# 1_P1.net
KiCad netlist of a schematic drawn in Altium Designer
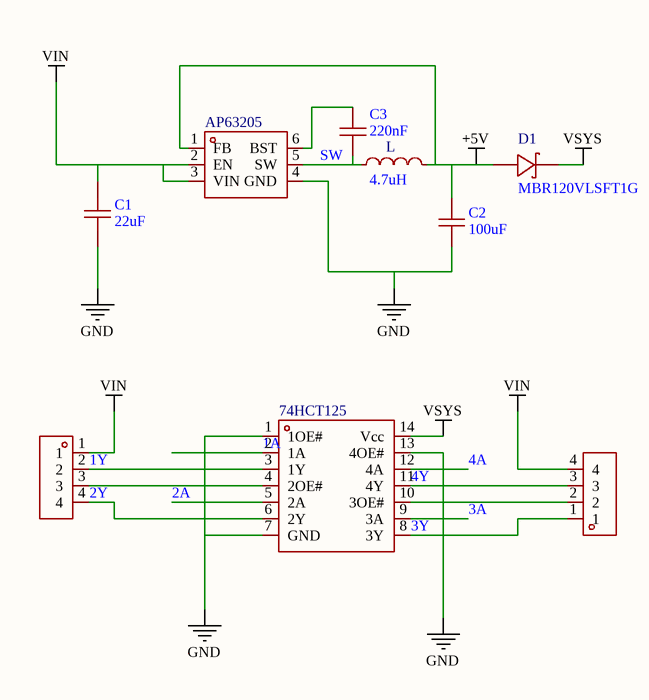
[diagram p0: 1_P1.schdoc]

(export (version "E")
  (design (tool "Eeschema 10.0.6"))
  (components
    (comp (ref "74HCT125")
      (value "74HCT125T14-13")
      (footprint "TSSOP-14_L5.0-W4.4-P0.65-LS6.4-BL")
      (fields (field (name "MANUFACTURER") "DIODES(美台)"))
      (libsource (lib "altium-import") (part "root_0_74HCT125T14-13_"))
    )
    (comp (ref "AP63205")
      (value "AP63205WU-7")
      (footprint "TSOT-23-6_L2.9-W1.6-P0.95-LS2.8-BL")
      (fields (field (name "MANUFACTURER") "DIODES(美台)"))
      (libsource (lib "altium-import") (part "root_0_AP63205WU-7_"))
    )
    (comp (ref "C1")
      (value "22uF")
      (footprint "C1210")
      (fields
        (field (name "MANUFACTURER") "TAIYO YUDEN(太诱)")
        (field (name "MANUFACTURER PART") "GMK325BJ226MM-P")
        (field (name "TOLERANCE") "±20%")
      )
      (libsource (lib "altium-import") (part "root_1_GMK325BJ226MM-P_"))
    )
    (comp (ref "C2")
      (value "100uF")
      (footprint "C1210")
      (fields
        (field (name "MANUFACTURER") "SAMSUNG(三星)")
        (field (name "MANUFACTURER PART") "CL32A107MQVNNNE")
        (field (name "TOLERANCE") "±20%")
      )
      (libsource (lib "altium-import") (part "root_1_CL32A107MQVNNNE_"))
    )
    (comp (ref "C3")
      (value "220nF")
      (footprint "C0603")
      (fields
        (field (name "MANUFACTURER") "SAMSUNG(三星)")
        (field (name "MANUFACTURER PART") "CL10B224KB8NNNC")
        (field (name "TOLERANCE") "±10%")
      )
      (libsource (lib "altium-import") (part "root_1_CL10B224KB8NNNC_"))
    )
    (comp (ref "CN1")
      (value "DB125-3.5-4P-GN-S")
      (footprint "CONN-TH_DB125-3.5-4P-GN")
      (fields (field (name "MANUFACTURER") "DORABO(地博电气)"))
      (libsource (lib "altium-import") (part "root_0_mirrored_DB125-3.5-4P-GN-S_"))
    )
    (comp (ref "CN2")
      (value "DB125-3.5-4P-GN-S")
      (footprint "CONN-TH_DB125-3.5-4P-GN")
      (fields (field (name "MANUFACTURER") "DORABO(地博电气)"))
      (libsource (lib "altium-import") (part "root_2_mirrored_DB125-3.5-4P-GN-S_"))
    )
    (comp (ref "D1")
      (value "MBR120VLSFT1G")
      (footprint "SOD-123F_L2.8-W1.8-LS3.7-RD")
      (fields (field (name "MANUFACTURER") "onsemi(安森美)"))
      (libsource (lib "altium-import") (part "root_0_mirrored_MBR120VLSFT1G_"))
    )
    (comp (ref "L")
      (value "4.7uH")
      (footprint "IND-SMD_L4.0-W4.0")
      (fields
        (field (name "MANUFACTURER") "ceaiya(柯爱亚)")
        (field (name "MANUFACTURER PART") "CR4030-4R7M")
        (field (name "TOLERANCE") "±20%")
      )
      (libsource (lib "altium-import") (part "root_0_CR4030-4R7M_"))
    )
  )
  (nets
    (net (code "1") (name "+5V") (class "Default")
      (node (ref "AP63205") (pin "1") (pinfunction "FB_1") (pintype "passive"))
      (node (ref "C2") (pin "2") (pinfunction "2_2") (pintype "passive"))
      (node (ref "D1") (pin "2") (pinfunction "A_2") (pintype "passive"))
      (node (ref "L") (pin "2") (pinfunction "2_2") (pintype "passive"))
    )
    (net (code "2") (name "/1A") (class "Default")
      (node (ref "74HCT125") (pin "2") (pinfunction "1A_2") (pintype "passive"))
    )
    (net (code "3") (name "/1Y") (class "Default")
      (node (ref "74HCT125") (pin "3") (pinfunction "1Y_3") (pintype "passive"))
      (node (ref "CN1") (pin "2") (pinfunction "2_2") (pintype "passive"))
    )
    (net (code "4") (name "/2A") (class "Default")
      (node (ref "74HCT125") (pin "5") (pinfunction "2A_5") (pintype "passive"))
    )
    (net (code "5") (name "/2Y") (class "Default")
      (node (ref "74HCT125") (pin "6") (pinfunction "2Y_6") (pintype "passive"))
      (node (ref "CN1") (pin "4") (pinfunction "4_4") (pintype "passive"))
    )
    (net (code "6") (name "/3A") (class "Default")
      (node (ref "74HCT125") (pin "9") (pinfunction "3A_9") (pintype "passive"))
    )
    (net (code "7") (name "/3Y") (class "Default")
      (node (ref "74HCT125") (pin "8") (pinfunction "3Y_8") (pintype "passive"))
      (node (ref "CN2") (pin "1") (pinfunction "1_1") (pintype "passive"))
    )
    (net (code "8") (name "/4A") (class "Default")
      (node (ref "74HCT125") (pin "12") (pinfunction "4A_12") (pintype "passive"))
    )
    (net (code "9") (name "/4Y") (class "Default")
      (node (ref "74HCT125") (pin "11") (pinfunction "4Y_11") (pintype "passive"))
      (node (ref "CN2") (pin "3") (pinfunction "3_3") (pintype "passive"))
    )
    (net (code "10") (name "/SW") (class "Default")
      (node (ref "AP63205") (pin "5") (pinfunction "SW_5") (pintype "passive"))
      (node (ref "C3") (pin "1") (pinfunction "1_1") (pintype "passive"))
      (node (ref "L") (pin "1") (pinfunction "1_1") (pintype "passive"))
    )
    (net (code "11") (name "GND") (class "Default")
      (node (ref "74HCT125") (pin "1") (pinfunction "1OE#_1") (pintype "passive"))
      (node (ref "74HCT125") (pin "10") (pinfunction "3OE#_10") (pintype "passive"))
      (node (ref "74HCT125") (pin "13") (pinfunction "4OE#_13") (pintype "passive"))
      (node (ref "74HCT125") (pin "4") (pinfunction "2OE#_4") (pintype "passive"))
      (node (ref "74HCT125") (pin "7") (pinfunction "GND_7") (pintype "passive"))
      (node (ref "AP63205") (pin "4") (pinfunction "GND_4") (pintype "passive"))
      (node (ref "C1") (pin "1") (pinfunction "1_1") (pintype "passive"))
      (node (ref "C2") (pin "1") (pinfunction "1_1") (pintype "passive"))
      (node (ref "CN1") (pin "3") (pinfunction "3_3") (pintype "passive"))
      (node (ref "CN2") (pin "2") (pinfunction "2_2") (pintype "passive"))
    )
    (net (code "12") (name "Net-(AP63205-BST)") (class "Default")
      (node (ref "AP63205") (pin "6") (pinfunction "BST_6") (pintype "passive"))
      (node (ref "C3") (pin "2") (pinfunction "2_2") (pintype "passive"))
    )
    (net (code "13") (name "VIN") (class "Default")
      (node (ref "AP63205") (pin "2") (pinfunction "EN_2") (pintype "passive"))
      (node (ref "AP63205") (pin "3") (pinfunction "VIN_3") (pintype "passive"))
      (node (ref "C1") (pin "2") (pinfunction "2_2") (pintype "passive"))
      (node (ref "CN1") (pin "1") (pinfunction "1_1") (pintype "passive"))
      (node (ref "CN2") (pin "4") (pinfunction "4_4") (pintype "passive"))
    )
    (net (code "14") (name "VSYS") (class "Default")
      (node (ref "74HCT125") (pin "14") (pinfunction "Vcc_14") (pintype "passive"))
      (node (ref "D1") (pin "1") (pinfunction "K_1") (pintype "passive"))
    )
  )
)
